# POWER.net
KiCad netlist of a schematic drawn in Altium Designer
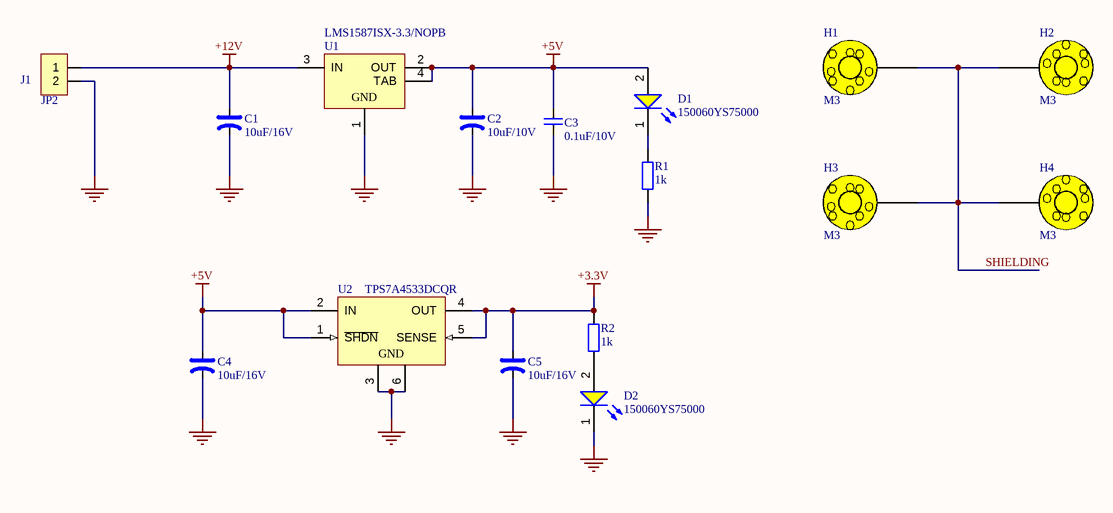
[diagram p0: POWER.SchDoc]

(export (version "E")
  (design (tool "Eeschema 10.0.6"))
  (components
    (comp (ref "C1")
      (value "10uF/16V")
      (footprint "CAP_MP_2012X170")
      (description "CAP_Polarization")
      (fields (field (name "PUBLISHER") "Altium Limited"))
      (libsource (lib "LABLIB") (part "CAP_TH"))
    )
    (comp (ref "C2")
      (value "10uF/10V")
      (footprint "CAP_MP_2012X170")
      (description "CAP_Polarization")
      (fields (field (name "PUBLISHER") "Altium Limited"))
      (libsource (lib "LABLIB") (part "CAP_TH"))
    )
    (comp (ref "C3")
      (value "0.1uF/10V")
      (footprint "CAP_C_1608X80")
      (description "CAP_Chip")
      (libsource (lib "LABLIB") (part "CAP_SMD"))
    )
    (comp (ref "C4")
      (value "10uF/16V")
      (footprint "CAP_MP_2012X170")
      (description "CAP_Polarization")
      (fields (field (name "PUBLISHER") "Altium Limited"))
      (libsource (lib "LABLIB") (part "CAP_TH"))
    )
    (comp (ref "C5")
      (value "10uF/16V")
      (footprint "CAP_MP_2012X170")
      (description "CAP_Polarization")
      (fields (field (name "PUBLISHER") "Altium Limited"))
      (libsource (lib "LABLIB") (part "CAP_TH"))
    )
    (comp (ref "D1")
      (value "150060YS75000")
      (footprint "WL-SMCW_0603_150060xx75000")
      (description "LED YELLOW CLEAR 0603 SMD")
      (libsource (lib "Altium Content Vault") (part "LED_Yellow_2A-1K"))
    )
    (comp (ref "D2")
      (value "150060YS75000")
      (footprint "WL-SMCW_0603_150060xx75000")
      (description "LED YELLOW CLEAR 0603 SMD")
      (libsource (lib "Altium Content Vault") (part "LED_Yellow_2A-1K"))
    )
    (comp (ref "H1") (value "M3") (footprint "HEX-M3") (libsource (lib "hex_M3") (part "HEX-M3")))
    (comp (ref "H2") (value "M3") (footprint "HEX-M3") (libsource (lib "hex_M3") (part "HEX-M3")))
    (comp (ref "H3") (value "M3") (footprint "HEX-M3") (libsource (lib "hex_M3") (part "HEX-M3")))
    (comp (ref "H4") (value "M3") (footprint "HEX-M3") (libsource (lib "hex_M3") (part "HEX-M3")))
    (comp (ref "J1")
      (value "JP2")
      (footprint "JP2-D1T")
      (description "WR-PHD 2.54 mm Angled Socket Header")
      (fields
        (field (name "MANUFACTURER") "Würth Elektronik eiSos GmbH")
        (field (name "PARTNO") "613002143121")
        (field (name "CREATED BY") "Karrer Zheng")
      )
      (libsource (lib "TechMT.VN_Lib") (part "JP2"))
    )
    (comp (ref "R1")
      (value "1k")
      (footprint "RES_C_1608X60")
      (description "RES")
      (libsource (lib "Altium_Lib_by_KhueNguyenCreator") (part "Tro 0603 1% 10k"))
    )
    (comp (ref "R2")
      (value "1k")
      (footprint "RES_C_1608X60")
      (description "RES")
      (libsource (lib "Altium_Lib_by_KhueNguyenCreator") (part "Tro 0603 1% 10k"))
    )
    (comp (ref "U1")
      (value "LMS1587ISX-3.3/NOPB")
      (footprint "TS3B_L")
      (description "3A Low Dropout Fast Response Regulators, 3-pin TO-263, Pb-Free")
      (fields (field (name "MANUFACTURER") "National Semiconductor"))
      (libsource (lib "Altium Content Vault") (part "PM-REG-LM1086-SOT4"))
    )
    (comp (ref "U2")
      (value "TPS7A4533DCQR")
      (footprint "DCQ0006A_M")
      (fields (field (name "MANUFACTURER") "Texas Instruments"))
      (libsource (lib "Altium Content Vault") (part "TI-TXXXXAXXXDCQ_KTTX"))
    )
  )
  (nets
    (net (code "1") (name "+3.3V") (class "Default")
      (node (ref "C5") (pin "1") (pinfunction "1_1") (pintype "passive"))
      (node (ref "R2") (pin "2") (pinfunction "2_2") (pintype "passive"))
      (node (ref "U2") (pin "4") (pinfunction "OUT_4") (pintype "power_in"))
      (node (ref "U2") (pin "5") (pinfunction "SENSE_5") (pintype "input"))
    )
    (net (code "2") (name "+5V") (class "Default")
      (node (ref "C2") (pin "1") (pinfunction "1_1") (pintype "passive"))
      (node (ref "C3") (pin "1") (pinfunction "1_1") (pintype "passive"))
      (node (ref "C4") (pin "1") (pinfunction "1_1") (pintype "passive"))
      (node (ref "D1") (pin "2") (pinfunction "A_2") (pintype "passive"))
      (node (ref "U1") (pin "2") (pinfunction "OUT_2") (pintype "power_in"))
      (node (ref "U1") (pin "4") (pinfunction "TAB_4") (pintype "power_in"))
      (node (ref "U2") (pin "1") (pinfunction "~{SHDN}_1") (pintype "input"))
      (node (ref "U2") (pin "2") (pinfunction "IN_2") (pintype "power_in"))
    )
    (net (code "3") (name "+12V") (class "Default")
      (node (ref "C1") (pin "1") (pinfunction "1_1") (pintype "passive"))
      (node (ref "J1") (pin "1") (pinfunction "1_1") (pintype "passive"))
      (node (ref "U1") (pin "3") (pinfunction "IN_3") (pintype "power_in"))
    )
    (net (code "4") (name "/SHIELDING") (class "Default")
      (node (ref "H1") (pin "1") (pinfunction "1_1") (pintype "power_in"))
      (node (ref "H2") (pin "1") (pinfunction "1_1") (pintype "power_in"))
      (node (ref "H3") (pin "1") (pinfunction "1_1") (pintype "power_in"))
      (node (ref "H4") (pin "1") (pinfunction "1_1") (pintype "power_in"))
    )
    (net (code "5") (name "GND") (class "Default")
      (node (ref "C1") (pin "2") (pinfunction "2_2") (pintype "passive"))
      (node (ref "C2") (pin "2") (pinfunction "2_2") (pintype "passive"))
      (node (ref "C3") (pin "2") (pinfunction "2_2") (pintype "passive"))
      (node (ref "C4") (pin "2") (pinfunction "2_2") (pintype "passive"))
      (node (ref "C5") (pin "2") (pinfunction "2_2") (pintype "passive"))
      (node (ref "D2") (pin "1") (pinfunction "K_1") (pintype "passive"))
      (node (ref "J1") (pin "2") (pinfunction "2_2") (pintype "passive"))
      (node (ref "R1") (pin "2") (pinfunction "2_2") (pintype "passive"))
      (node (ref "U1") (pin "1") (pinfunction "GND_1") (pintype "power_in"))
      (node (ref "U2") (pin "3") (pinfunction "GND_3") (pintype "power_in"))
      (node (ref "U2") (pin "6") (pinfunction "GND_6") (pintype "power_in"))
    )
    (net (code "6") (name "Net-(D1-K)") (class "Default")
      (node (ref "D1") (pin "1") (pinfunction "K_1") (pintype "passive"))
      (node (ref "R1") (pin "1") (pinfunction "1_1") (pintype "passive"))
    )
    (net (code "7") (name "Net-(D2-A)") (class "Default")
      (node (ref "D2") (pin "2") (pinfunction "A_2") (pintype "passive"))
      (node (ref "R2") (pin "1") (pinfunction "1_1") (pintype "passive"))
    )
  )
)
